# LifeBoardV1_2_stm.net
KiCad netlist of a schematic drawn in EAGLE
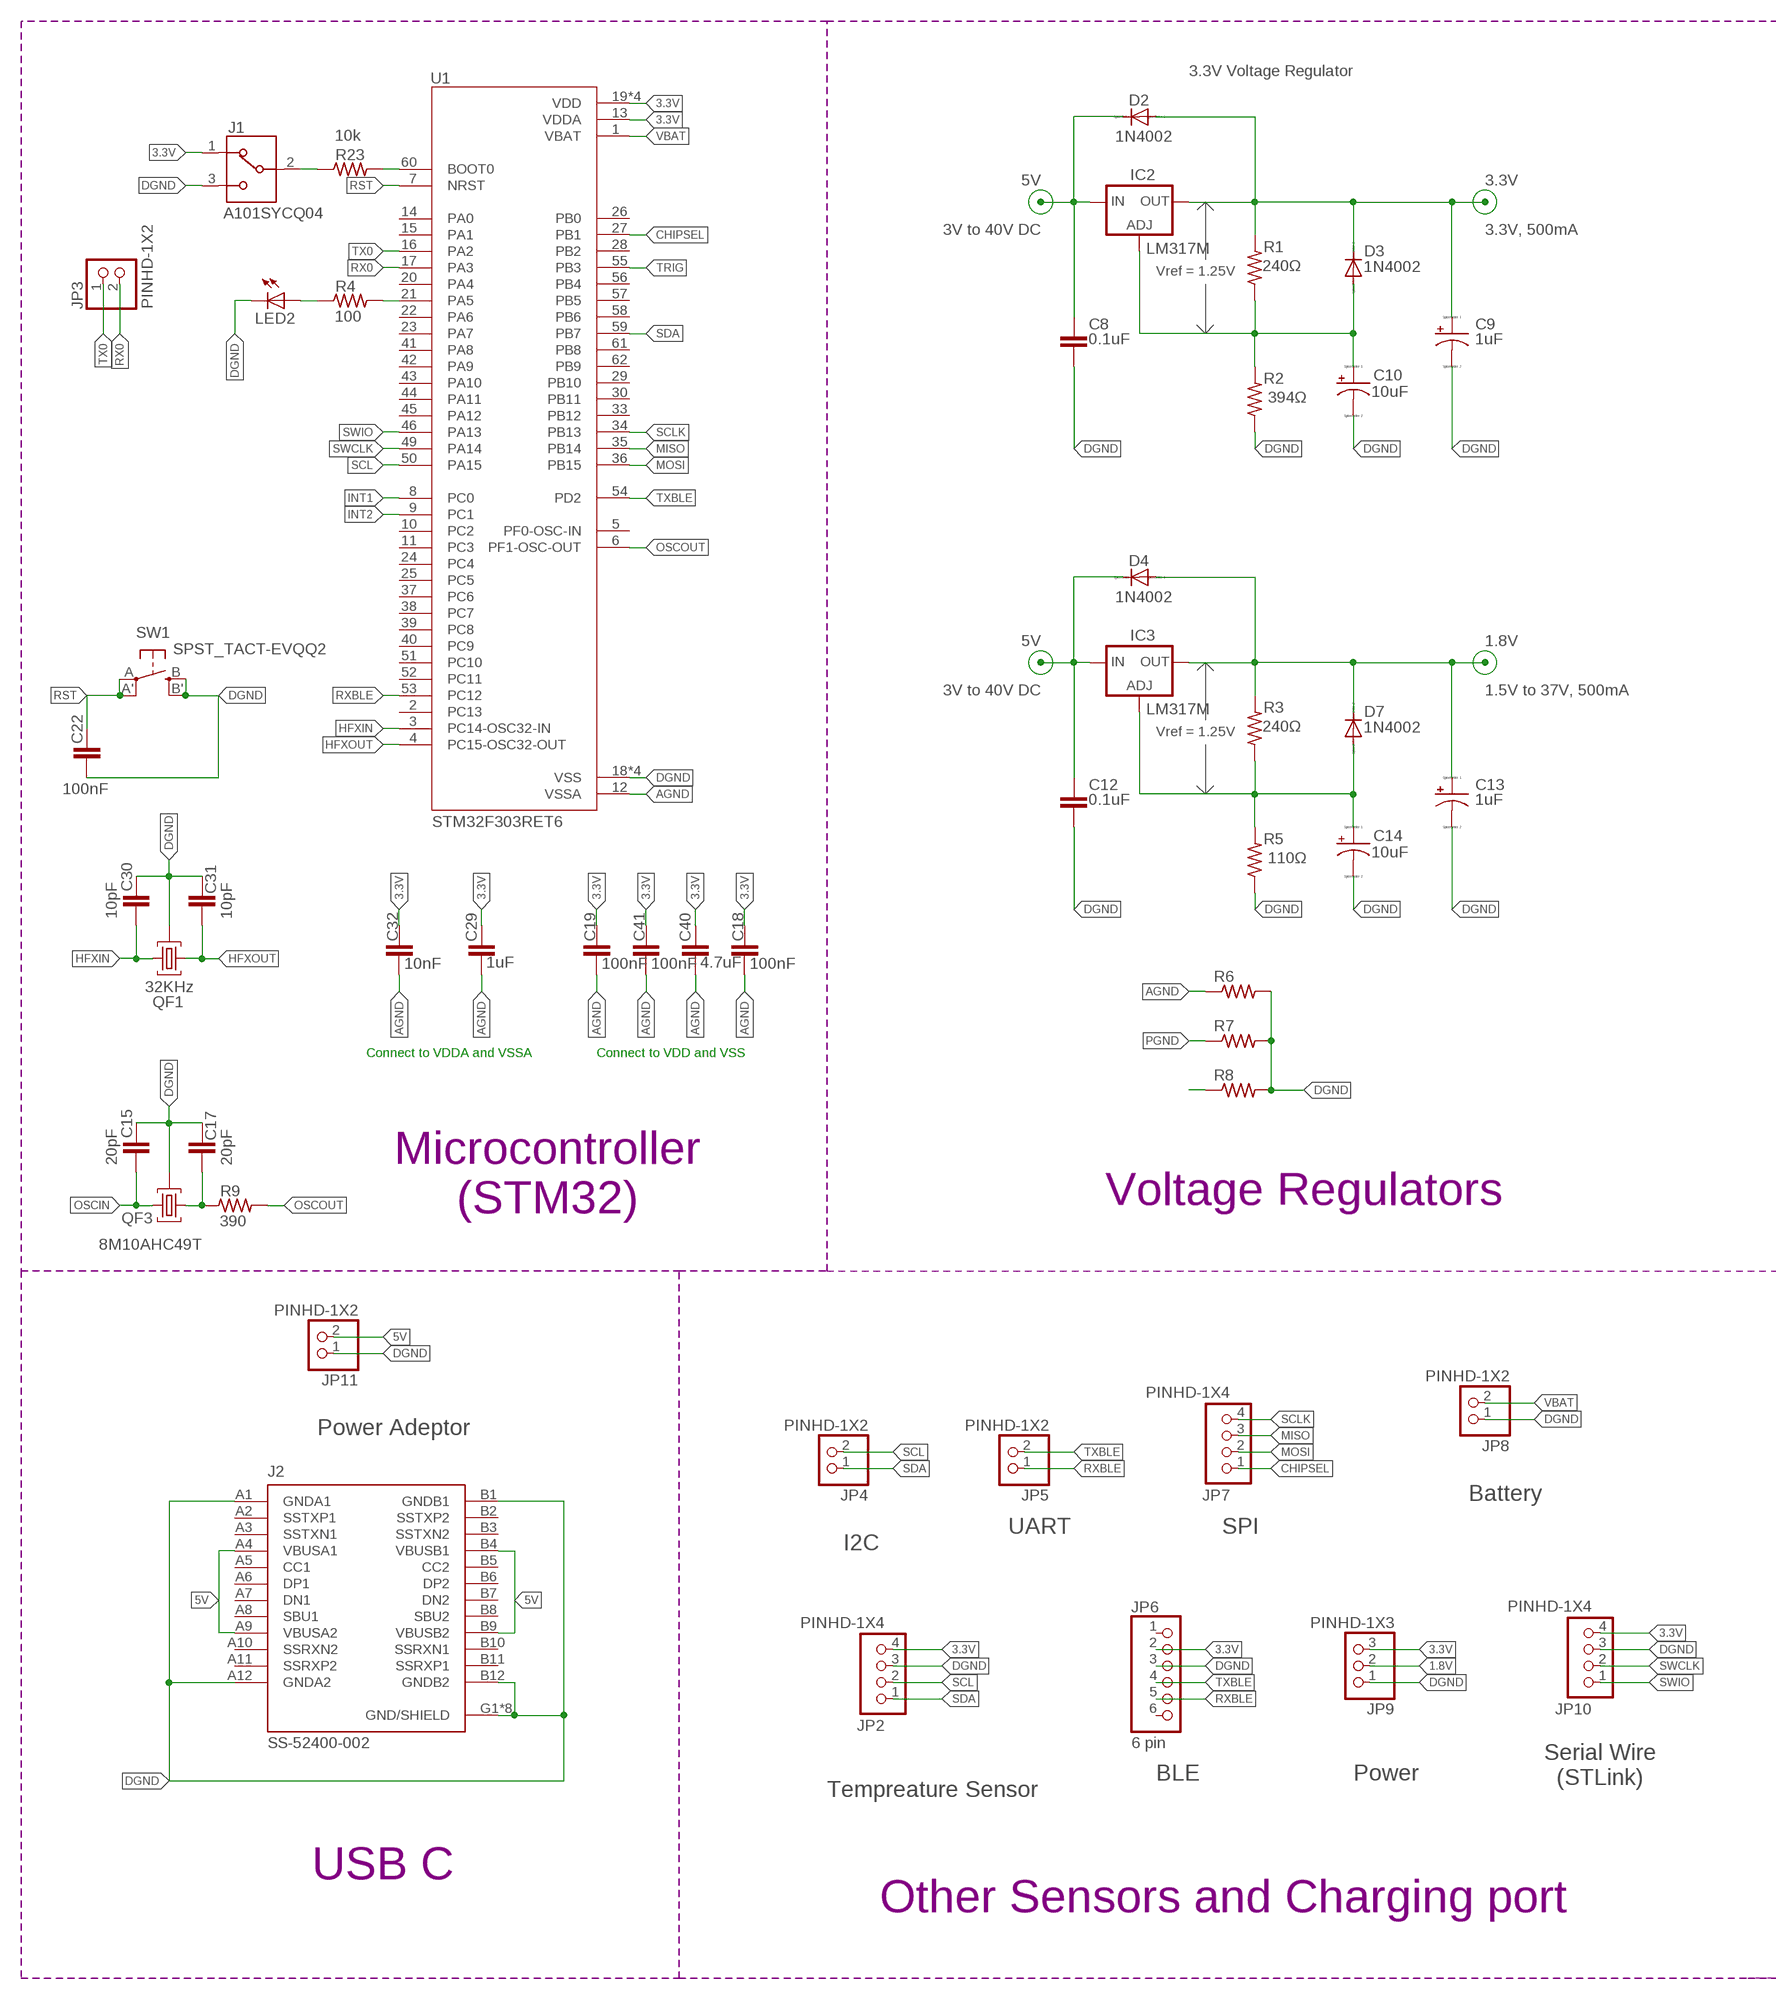
[diagram p0: schematic, sheet 1, part 1 of 2]
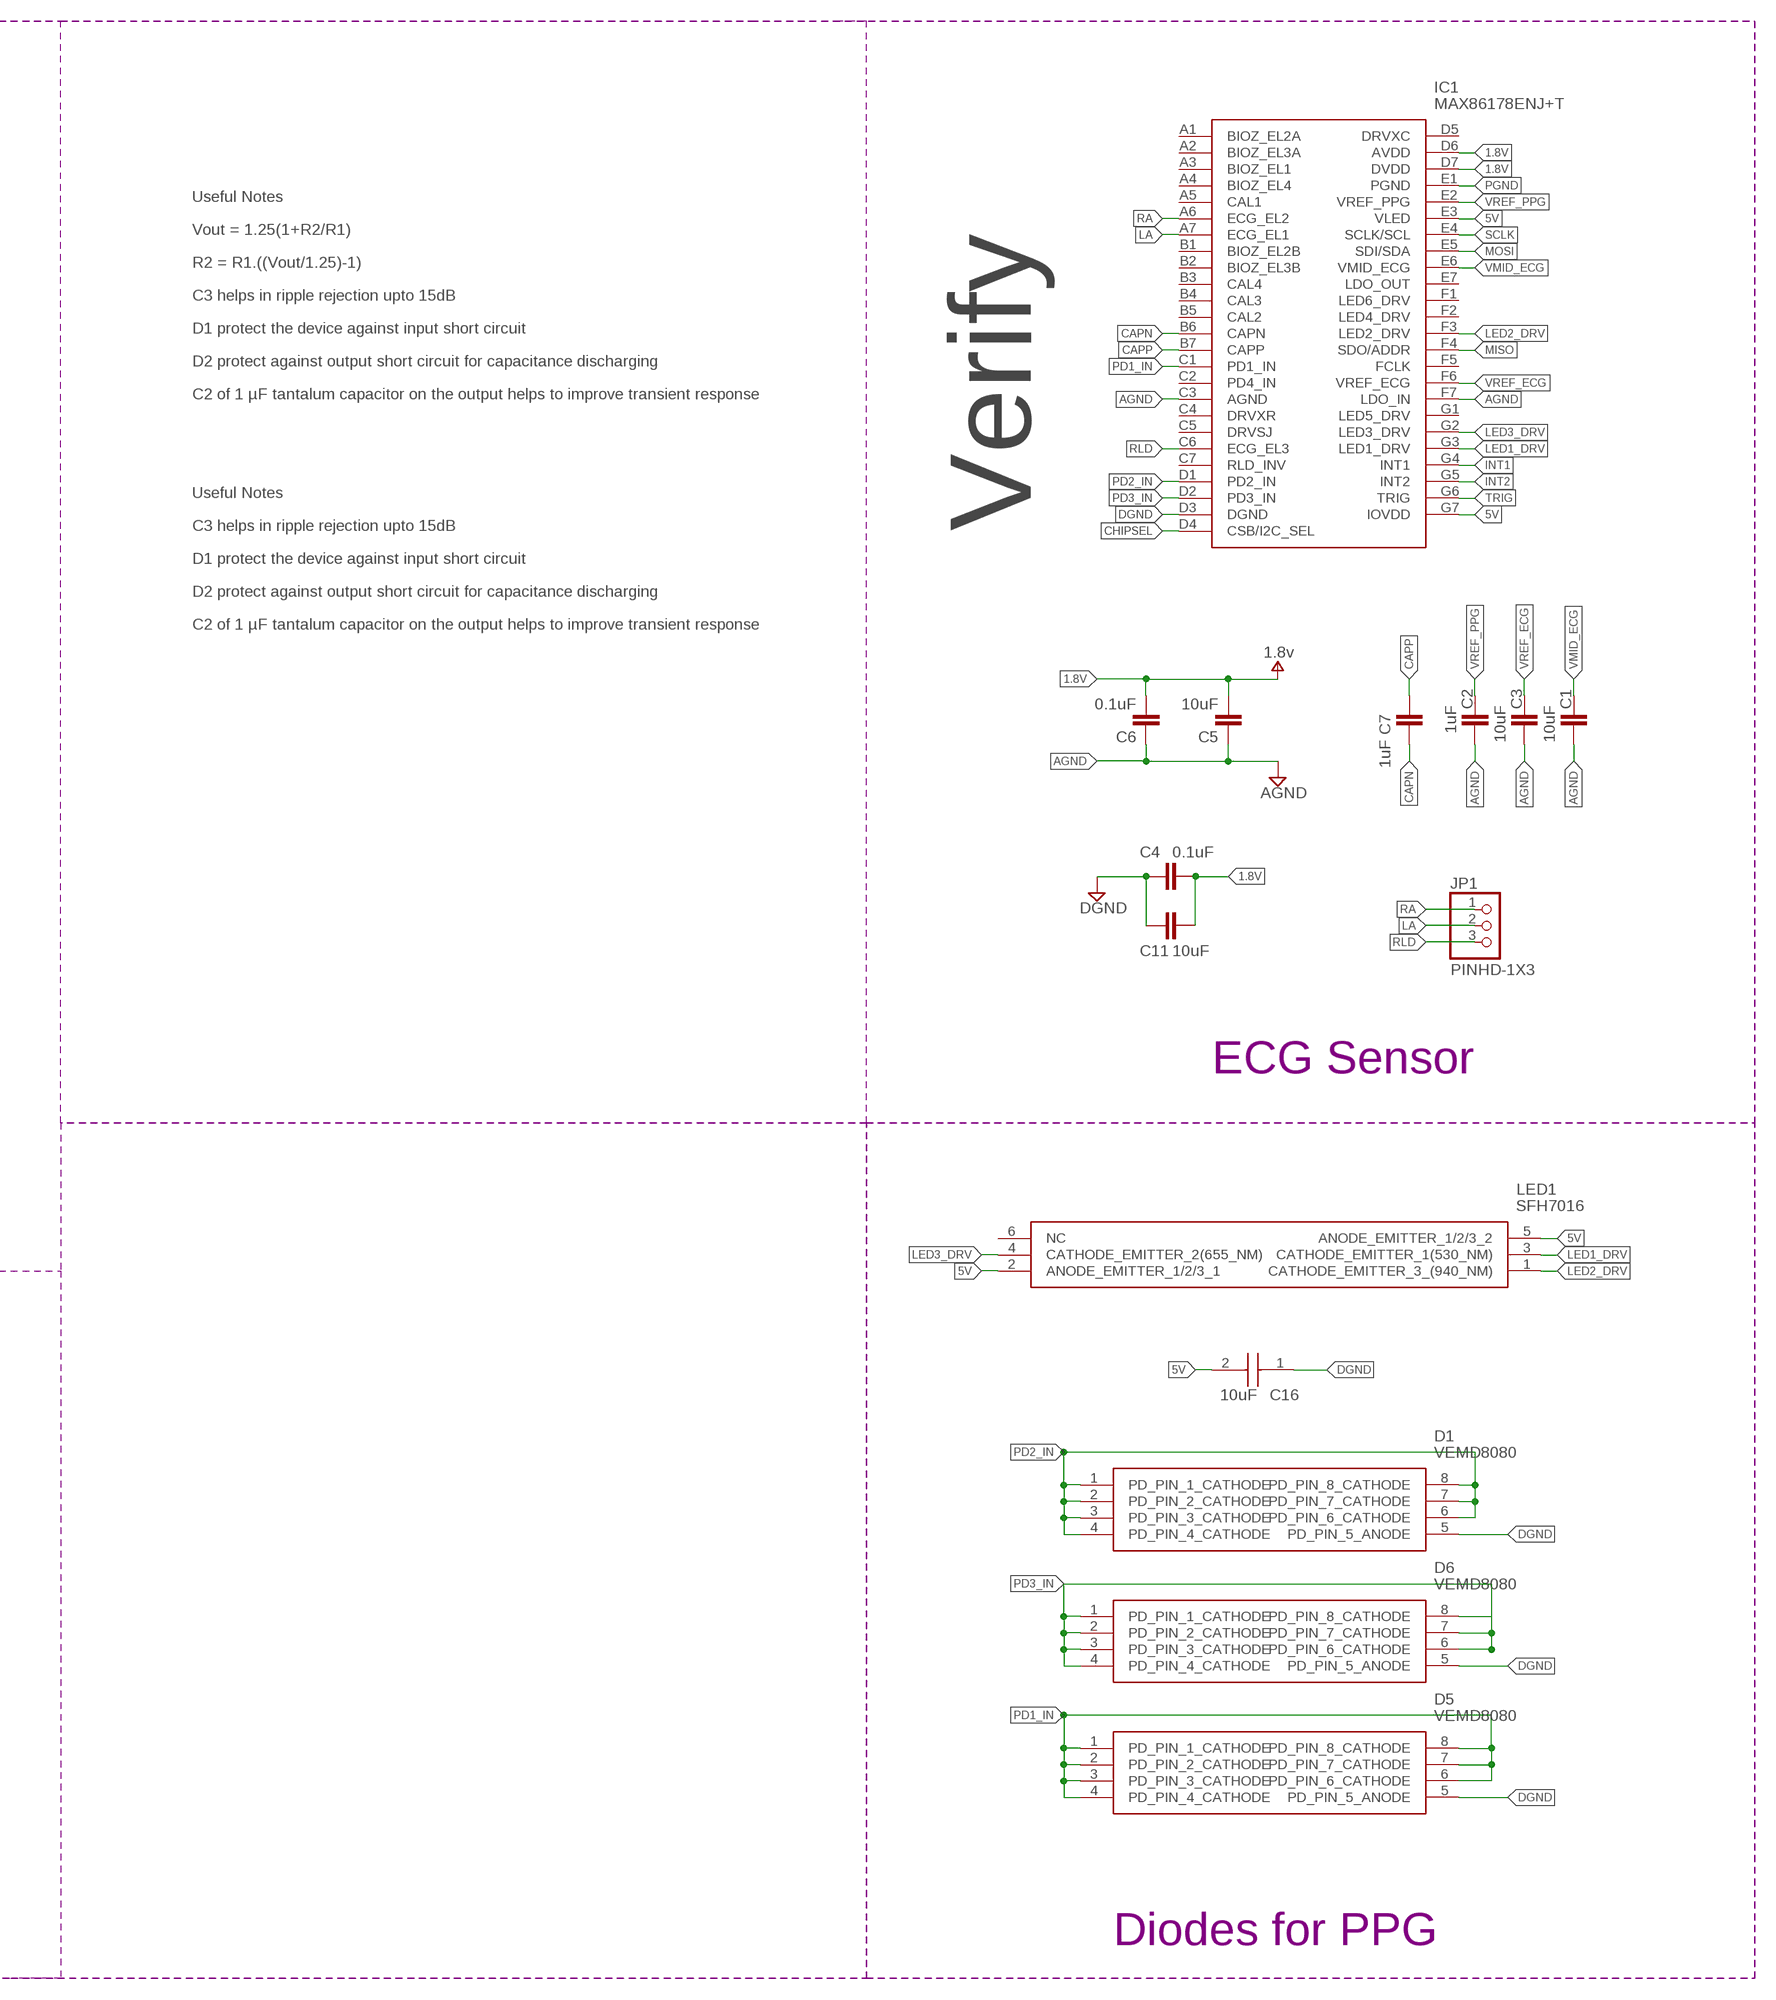
[diagram p1: schematic, sheet 1, part 2 of 2]

(export (version "E")
  (design (tool "Eeschema 10.0.6"))
  (components
    (comp (ref "C1")
      (value "10uF")
      (footprint "eagle-import:C0805")
      (libsource (lib "eagle-import") (part "C-EUC0805"))
    )
    (comp (ref "C2")
      (value "1uF")
      (footprint "eagle-import:C0805")
      (libsource (lib "eagle-import") (part "C-EUC0805"))
    )
    (comp (ref "C3")
      (value "10uF")
      (footprint "eagle-import:C0805")
      (libsource (lib "eagle-import") (part "C-EUC0805"))
    )
    (comp (ref "C4")
      (value "0.1uF")
      (footprint "eagle-import:C0805")
      (libsource (lib "eagle-import") (part "C-EUC0805"))
    )
    (comp (ref "C5")
      (value "10uF")
      (footprint "eagle-import:C0805")
      (libsource (lib "eagle-import") (part "C-EUC0805"))
    )
    (comp (ref "C6")
      (value "0.1uF")
      (footprint "eagle-import:C0805")
      (libsource (lib "eagle-import") (part "C-EUC0805"))
    )
    (comp (ref "C7")
      (value "1uF")
      (footprint "eagle-import:C0805")
      (libsource (lib "eagle-import") (part "C-EUC0805"))
    )
    (comp (ref "C8")
      (value "0.1uF")
      (footprint "eagle-import:C075-052X106")
      (libsource (lib "eagle-import") (part "C-EU075-052X106"))
    )
    (comp (ref "C9")
      (value "1uF")
      (footprint "eagle-import:085CS_1AR")
      (libsource (lib "eagle-import") (part "CPOL-US085CS-1AR"))
    )
    (comp (ref "C10")
      (value "10uF")
      (footprint "eagle-import:085CS_1AR")
      (libsource (lib "eagle-import") (part "CPOL-US085CS-1AR"))
    )
    (comp (ref "C11")
      (value "10uF")
      (footprint "eagle-import:C0805")
      (libsource (lib "eagle-import") (part "C-EUC0805"))
    )
    (comp (ref "C12")
      (value "0.1uF")
      (footprint "eagle-import:C075-052X106")
      (libsource (lib "eagle-import") (part "C-EU075-052X106"))
    )
    (comp (ref "C13")
      (value "1uF")
      (footprint "eagle-import:085CS_1AR")
      (libsource (lib "eagle-import") (part "CPOL-US085CS-1AR"))
    )
    (comp (ref "C14")
      (value "10uF")
      (footprint "eagle-import:085CS_1AR")
      (libsource (lib "eagle-import") (part "CPOL-US085CS-1AR"))
    )
    (comp (ref "C15")
      (value "20pF")
      (footprint "eagle-import:C0805")
      (libsource (lib "eagle-import") (part "C-EUC0805"))
    )
    (comp (ref "C16")
      (value "10uF")
      (footprint "eagle-import:CAPC1608X90N")
      (fields
        (field (name "ARROW_PART_NUMBER") "GRM188R61E106MA73L")
        (field (name "MOUSER_PART_NUMBER") "81-GRM188R61E106MA3L")
      )
      (libsource (lib "eagle-import") (part "GRM188R61E106MA73L"))
    )
    (comp (ref "C17")
      (value "20pF")
      (footprint "eagle-import:C0805")
      (libsource (lib "eagle-import") (part "C-EUC0805"))
    )
    (comp (ref "C18")
      (value "100nF")
      (footprint "eagle-import:C0805")
      (libsource (lib "eagle-import") (part "C-EUC0805"))
    )
    (comp (ref "C19")
      (value "100nF")
      (footprint "eagle-import:C0805")
      (libsource (lib "eagle-import") (part "C-EUC0805"))
    )
    (comp (ref "C22")
      (value "100nF")
      (footprint "eagle-import:C0805")
      (libsource (lib "eagle-import") (part "C-EUC0805"))
    )
    (comp (ref "C29")
      (value "1uF")
      (footprint "eagle-import:C0805")
      (libsource (lib "eagle-import") (part "C-EUC0805"))
    )
    (comp (ref "C30")
      (value "10pF")
      (footprint "eagle-import:C0805")
      (libsource (lib "eagle-import") (part "C-EUC0805"))
    )
    (comp (ref "C31")
      (value "10pF")
      (footprint "eagle-import:C0805")
      (libsource (lib "eagle-import") (part "C-EUC0805"))
    )
    (comp (ref "C32")
      (value "10nF")
      (footprint "eagle-import:C0805")
      (libsource (lib "eagle-import") (part "C-EUC0805"))
    )
    (comp (ref "C40")
      (value "4.7uF")
      (footprint "eagle-import:C0805")
      (libsource (lib "eagle-import") (part "C-EUC0805"))
    )
    (comp (ref "C41")
      (value "100nF")
      (footprint "eagle-import:C0805")
      (libsource (lib "eagle-import") (part "C-EUC0805"))
    )
    (comp (ref "D1")
      (value "VEMD8080")
      (footprint "eagle-import:VEMD8080")
      (fields (field (name "MOUSER_PART_NUMBER") "78-VEMD8080"))
      (libsource (lib "eagle-import") (part "VEMD8080"))
    )
    (comp (ref "D2")
      (value "1N4002")
      (footprint "eagle-import:DO41-10")
      (libsource (lib "eagle-import") (part "1N4004"))
    )
    (comp (ref "D3")
      (value "1N4002")
      (footprint "eagle-import:DO41-10")
      (libsource (lib "eagle-import") (part "1N4004"))
    )
    (comp (ref "D4")
      (value "1N4002")
      (footprint "eagle-import:DO41-10")
      (libsource (lib "eagle-import") (part "1N4004"))
    )
    (comp (ref "D5")
      (value "VEMD8080")
      (footprint "eagle-import:VEMD8080")
      (fields (field (name "MOUSER_PART_NUMBER") "78-VEMD8080"))
      (libsource (lib "eagle-import") (part "VEMD8080"))
    )
    (comp (ref "D6")
      (value "VEMD8080")
      (footprint "eagle-import:VEMD8080")
      (fields (field (name "MOUSER_PART_NUMBER") "78-VEMD8080"))
      (libsource (lib "eagle-import") (part "VEMD8080"))
    )
    (comp (ref "D7")
      (value "1N4002")
      (footprint "eagle-import:DO41-10")
      (libsource (lib "eagle-import") (part "1N4004"))
    )
    (comp (ref "IC1")
      (value "MAX86178ENJ+T")
      (footprint "eagle-import:BGA49C35P7X7_277X257X50")
      (fields (field (name "MOUSER_PART_NUMBER") "700-MAX86178ENJ+T"))
      (libsource (lib "eagle-import") (part "MAX86178ENJ+T"))
    )
    (comp (ref "IC2")
      (value "LM317MBSTT3")
      (footprint "eagle-import:SOT223")
      (fields (field (name "PARTNUMBER") "LM317M"))
      (libsource (lib "eagle-import") (part "LM317?MBSTT3"))
    )
    (comp (ref "IC3")
      (value "LM317MBSTT3")
      (footprint "eagle-import:SOT223")
      (fields (field (name "PARTNUMBER") "LM317M"))
      (libsource (lib "eagle-import") (part "LM317?MBSTT3"))
    )
    (comp (ref "J1")
      (value "A101SYCQ04")
      (footprint "eagle-import:TE_A101SYCQ04")
      (fields (field (name "COMMENT") "4-1825136-5") (field (name "MF") "TE Connectivity"))
      (libsource (lib "eagle-import") (part "A101SYCQ04"))
    )
    (comp (ref "J2")
      (value "SS-52400-002")
      (footprint "eagle-import:BELFUSE_SS-52400-002")
      (fields (field (name "MF") "Stewart Connector"))
      (libsource (lib "eagle-import") (part "SS-52400-002"))
    )
    (comp (ref "JP1")
      (value "PINHD-1X3")
      (footprint "eagle-import:1X03")
      (libsource (lib "eagle-import") (part "PINHD-1X3"))
    )
    (comp (ref "JP2")
      (value "PINHD-1X4")
      (footprint "eagle-import:1X04")
      (libsource (lib "eagle-import") (part "PINHD-1X4"))
    )
    (comp (ref "JP3")
      (value "PINHD-1X2")
      (footprint "eagle-import:1X02")
      (libsource (lib "eagle-import") (part "PINHD-1X2"))
    )
    (comp (ref "JP4")
      (value "PINHD-1X2")
      (footprint "eagle-import:1X02")
      (libsource (lib "eagle-import") (part "PINHD-1X2"))
    )
    (comp (ref "JP5")
      (value "PINHD-1X2")
      (footprint "eagle-import:1X02")
      (libsource (lib "eagle-import") (part "PINHD-1X2"))
    )
    (comp (ref "JP6")
      (value "6 pin")
      (footprint "eagle-import:1X06")
      (libsource (lib "eagle-import") (part "PINHD-1X6"))
    )
    (comp (ref "JP7")
      (value "PINHD-1X4")
      (footprint "eagle-import:1X04")
      (libsource (lib "eagle-import") (part "PINHD-1X4"))
    )
    (comp (ref "JP8")
      (value "PINHD-1X2")
      (footprint "eagle-import:1X02")
      (libsource (lib "eagle-import") (part "PINHD-1X2"))
    )
    (comp (ref "JP9")
      (value "PINHD-1X3")
      (footprint "eagle-import:1X03")
      (libsource (lib "eagle-import") (part "PINHD-1X3"))
    )
    (comp (ref "JP10")
      (value "PINHD-1X4")
      (footprint "eagle-import:1X04")
      (libsource (lib "eagle-import") (part "PINHD-1X4"))
    )
    (comp (ref "JP11")
      (value "PINHD-1X2")
      (footprint "eagle-import:1X02")
      (libsource (lib "eagle-import") (part "PINHD-1X2"))
    )
    (comp (ref "LED1")
      (value "SFH7016")
      (footprint "eagle-import:SFH7016")
      (libsource (lib "eagle-import") (part "SFH7016"))
    )
    (comp (ref "LED2")
      (value "LEDCHIP-LED0805")
      (footprint "eagle-import:CHIP-LED0805")
      (libsource (lib "eagle-import") (part "LEDCHIP-LED0805"))
    )
    (comp (ref "QF1")
      (value "32KHz")
      (footprint "eagle-import:HC49U")
      (libsource (lib "eagle-import") (part "8M10AHC49T"))
    )
    (comp (ref "QF3")
      (value "8M10AHC49T")
      (footprint "eagle-import:HC49U")
      (libsource (lib "eagle-import") (part "8M10AHC49T"))
    )
    (comp (ref "R1")
      (value "240Ω")
      (footprint "eagle-import:M0805")
      (libsource (lib "eagle-import") (part "resistor_348_R-US_M0805"))
    )
    (comp (ref "R2")
      (value "394Ω")
      (footprint "eagle-import:M0805")
      (libsource (lib "eagle-import") (part "resistor_348_R-US_M0805"))
    )
    (comp (ref "R3")
      (value "240Ω")
      (footprint "eagle-import:M0805")
      (libsource (lib "eagle-import") (part "resistor_348_R-US_M0805"))
    )
    (comp (ref "R4")
      (value "100")
      (footprint "eagle-import:M1206")
      (libsource (lib "eagle-import") (part "R-US_M1206"))
    )
    (comp (ref "R5")
      (value "110Ω")
      (footprint "eagle-import:M0805")
      (libsource (lib "eagle-import") (part "resistor_348_R-US_M0805"))
    )
    (comp (ref "R6")
      (value "R-US_M0805")
      (footprint "eagle-import:M0805")
      (libsource (lib "eagle-import") (part "R-US_M0805"))
    )
    (comp (ref "R7")
      (value "R-US_M0805")
      (footprint "eagle-import:M0805")
      (libsource (lib "eagle-import") (part "R-US_M0805"))
    )
    (comp (ref "R8")
      (value "R-US_M0805")
      (footprint "eagle-import:M0805")
      (libsource (lib "eagle-import") (part "R-US_M0805"))
    )
    (comp (ref "R9")
      (value "390")
      (footprint "eagle-import:M1206")
      (libsource (lib "eagle-import") (part "R-US_M1206"))
    )
    (comp (ref "R23")
      (value "10k")
      (footprint "eagle-import:M1206")
      (libsource (lib "eagle-import") (part "R-US_M1206"))
    )
    (comp (ref "SW1")
      (value "SPST_TACT-EVQQ2")
      (footprint "eagle-import:EVQ-Q2")
      (libsource (lib "eagle-import") (part "SPST_TACT-EVQQ2"))
    )
    (comp (ref "U1")
      (value "STM32F303RET6")
      (footprint "eagle-import:QFP50P1200X1200X160-64N")
      (fields (field (name "MF") "STMicroelectronics"))
      (libsource (lib "eagle-import") (part "STM32F303RET6"))
    )
  )
  (nets
    (net (code "1") (name "1.8V") (class "Default")
      (node (ref "C11") (pin "2") (pinfunction "2_2") (pintype "passive"))
      (node (ref "C13") (pin "+") (pinfunction "+_+") (pintype "passive"))
      (node (ref "C4") (pin "2") (pinfunction "2_2") (pintype "passive"))
      (node (ref "C5") (pin "2") (pinfunction "2_2") (pintype "passive"))
      (node (ref "C6") (pin "2") (pinfunction "2_2") (pintype "passive"))
      (node (ref "D4") (pin "A") (pinfunction "A_A") (pintype "passive"))
      (node (ref "D7") (pin "C") (pinfunction "C_C") (pintype "passive"))
      (node (ref "IC1") (pin "D6") (pinfunction "AVDD_D6") (pintype "bidirectional"))
      (node (ref "IC1") (pin "D7") (pinfunction "DVDD_D7") (pintype "bidirectional"))
      (node (ref "IC3") (pin "4") (pinfunction "OUT_4") (pintype "passive"))
      (node (ref "JP9") (pin "2") (pinfunction "2_2") (pintype "passive"))
      (node (ref "R3") (pin "2") (pinfunction "2_2") (pintype "passive"))
    )
    (net (code "2") (name "3.3V") (class "Default")
      (node (ref "C18") (pin "1") (pinfunction "1_1") (pintype "passive"))
      (node (ref "C19") (pin "1") (pinfunction "1_1") (pintype "passive"))
      (node (ref "C29") (pin "1") (pinfunction "1_1") (pintype "passive"))
      (node (ref "C32") (pin "1") (pinfunction "1_1") (pintype "passive"))
      (node (ref "C40") (pin "1") (pinfunction "1_1") (pintype "passive"))
      (node (ref "C41") (pin "1") (pinfunction "1_1") (pintype "passive"))
      (node (ref "C9") (pin "+") (pinfunction "+_+") (pintype "passive"))
      (node (ref "D2") (pin "A") (pinfunction "A_A") (pintype "passive"))
      (node (ref "D3") (pin "C") (pinfunction "C_C") (pintype "passive"))
      (node (ref "IC2") (pin "4") (pinfunction "OUT_4") (pintype "passive"))
      (node (ref "J1") (pin "1") (pinfunction "1_1") (pintype "passive"))
      (node (ref "JP10") (pin "4") (pinfunction "4_4") (pintype "passive"))
      (node (ref "JP2") (pin "4") (pinfunction "4_4") (pintype "passive"))
      (node (ref "JP6") (pin "2") (pinfunction "2_2") (pintype "passive"))
      (node (ref "JP9") (pin "3") (pinfunction "3_3") (pintype "passive"))
      (node (ref "R1") (pin "2") (pinfunction "2_2") (pintype "passive"))
      (node (ref "U1") (pin "13") (pinfunction "VDDA_13") (pintype "power_in"))
      (node (ref "U1") (pin "19") (pinfunction "VDD_19") (pintype "power_in"))
      (node (ref "U1") (pin "32") (pinfunction "VDD_32") (pintype "power_in"))
      (node (ref "U1") (pin "48") (pinfunction "VDD_48") (pintype "power_in"))
      (node (ref "U1") (pin "64") (pinfunction "VDD_64") (pintype "power_in"))
    )
    (net (code "3") (name "5V") (class "Default")
      (node (ref "C12") (pin "1") (pinfunction "1_1") (pintype "passive"))
      (node (ref "C16") (pin "2") (pinfunction "2_2") (pintype "bidirectional"))
      (node (ref "C8") (pin "1") (pinfunction "1_1") (pintype "passive"))
      (node (ref "D2") (pin "C") (pinfunction "C_C") (pintype "passive"))
      (node (ref "D4") (pin "C") (pinfunction "C_C") (pintype "passive"))
      (node (ref "IC1") (pin "E3") (pinfunction "VLED_E3") (pintype "bidirectional"))
      (node (ref "IC1") (pin "G7") (pinfunction "IOVDD_G7") (pintype "bidirectional"))
      (node (ref "IC2") (pin "3") (pinfunction "IN_3") (pintype "input"))
      (node (ref "IC3") (pin "3") (pinfunction "IN_3") (pintype "input"))
      (node (ref "J2") (pin "A4") (pinfunction "VBUSA1_A4") (pintype "power_in"))
      (node (ref "J2") (pin "A9") (pinfunction "VBUSA2_A9") (pintype "power_in"))
      (node (ref "J2") (pin "B4") (pinfunction "VBUSB1_B4") (pintype "power_in"))
      (node (ref "J2") (pin "B9") (pinfunction "VBUSB2_B9") (pintype "power_in"))
      (node (ref "JP11") (pin "2") (pinfunction "2_2") (pintype "passive"))
      (node (ref "LED1") (pin "2") (pinfunction "ANODE_EMITTER_1/2/3_1_2") (pintype "bidirectional"))
      (node (ref "LED1") (pin "5") (pinfunction "ANODE_EMITTER_1/2/3_2_5") (pintype "bidirectional"))
    )
    (net (code "4") (name "AGND") (class "Default")
      (node (ref "C1") (pin "1") (pinfunction "1_1") (pintype "passive"))
      (node (ref "C18") (pin "2") (pinfunction "2_2") (pintype "passive"))
      (node (ref "C19") (pin "2") (pinfunction "2_2") (pintype "passive"))
      (node (ref "C2") (pin "1") (pinfunction "1_1") (pintype "passive"))
      (node (ref "C29") (pin "2") (pinfunction "2_2") (pintype "passive"))
      (node (ref "C3") (pin "1") (pinfunction "1_1") (pintype "passive"))
      (node (ref "C32") (pin "2") (pinfunction "2_2") (pintype "passive"))
      (node (ref "C40") (pin "2") (pinfunction "2_2") (pintype "passive"))
      (node (ref "C41") (pin "2") (pinfunction "2_2") (pintype "passive"))
      (node (ref "C5") (pin "1") (pinfunction "1_1") (pintype "passive"))
      (node (ref "C6") (pin "1") (pinfunction "1_1") (pintype "passive"))
      (node (ref "IC1") (pin "C3") (pinfunction "AGND_C3") (pintype "bidirectional"))
      (node (ref "IC1") (pin "F7") (pinfunction "LDO_IN_F7") (pintype "bidirectional"))
      (node (ref "R6") (pin "1") (pinfunction "1_1") (pintype "passive"))
      (node (ref "U1") (pin "12") (pinfunction "VSSA_12") (pintype "power_in"))
    )
    (net (code "5") (name "CAPN") (class "Default")
      (node (ref "C7") (pin "2") (pinfunction "2_2") (pintype "passive"))
      (node (ref "IC1") (pin "B6") (pinfunction "CAPN_B6") (pintype "bidirectional"))
    )
    (net (code "6") (name "CAPP") (class "Default")
      (node (ref "C7") (pin "1") (pinfunction "1_1") (pintype "passive"))
      (node (ref "IC1") (pin "B7") (pinfunction "CAPP_B7") (pintype "bidirectional"))
    )
    (net (code "7") (name "CHIPSEL") (class "Default")
      (node (ref "IC1") (pin "D4") (pinfunction "CSB/I2C_SEL_D4") (pintype "bidirectional"))
      (node (ref "JP7") (pin "1") (pinfunction "1_1") (pintype "passive"))
      (node (ref "U1") (pin "27") (pinfunction "PB1_27") (pintype "bidirectional"))
    )
    (net (code "8") (name "DGND") (class "Default")
      (node (ref "C10") (pin "-") (pinfunction "-_-") (pintype "passive"))
      (node (ref "C11") (pin "1") (pinfunction "1_1") (pintype "passive"))
      (node (ref "C12") (pin "2") (pinfunction "2_2") (pintype "passive"))
      (node (ref "C13") (pin "-") (pinfunction "-_-") (pintype "passive"))
      (node (ref "C14") (pin "-") (pinfunction "-_-") (pintype "passive"))
      (node (ref "C15") (pin "1") (pinfunction "1_1") (pintype "passive"))
      (node (ref "C16") (pin "1") (pinfunction "1_1") (pintype "bidirectional"))
      (node (ref "C17") (pin "1") (pinfunction "1_1") (pintype "passive"))
      (node (ref "C22") (pin "2") (pinfunction "2_2") (pintype "passive"))
      (node (ref "C30") (pin "1") (pinfunction "1_1") (pintype "passive"))
      (node (ref "C31") (pin "1") (pinfunction "1_1") (pintype "passive"))
      (node (ref "C4") (pin "1") (pinfunction "1_1") (pintype "passive"))
      (node (ref "C8") (pin "2") (pinfunction "2_2") (pintype "passive"))
      (node (ref "C9") (pin "-") (pinfunction "-_-") (pintype "passive"))
      (node (ref "D1") (pin "5") (pinfunction "PD_PIN_5_ANODE_5") (pintype "bidirectional"))
      (node (ref "D5") (pin "5") (pinfunction "PD_PIN_5_ANODE_5") (pintype "bidirectional"))
      (node (ref "D6") (pin "5") (pinfunction "PD_PIN_5_ANODE_5") (pintype "bidirectional"))
      (node (ref "IC1") (pin "D3") (pinfunction "DGND_D3") (pintype "bidirectional"))
      (node (ref "J1") (pin "3") (pinfunction "3_3") (pintype "passive"))
      (node (ref "J2") (pin "A1") (pinfunction "GNDA1_A1") (pintype "power_in"))
      (node (ref "J2") (pin "A12") (pinfunction "GNDA2_A12") (pintype "power_in"))
      (node (ref "J2") (pin "B1") (pinfunction "GNDB1_B1") (pintype "power_in"))
      (node (ref "J2") (pin "B12") (pinfunction "GNDB2_B12") (pintype "power_in"))
      (node (ref "J2") (pin "G1") (pinfunction "GND/SHIELD_G1") (pintype "power_in"))
      (node (ref "J2") (pin "G2") (pinfunction "GND/SHIELD_G2") (pintype "power_in"))
      (node (ref "J2") (pin "G3") (pinfunction "GND/SHIELD_G3") (pintype "power_in"))
      (node (ref "J2") (pin "G4") (pinfunction "GND/SHIELD_G4") (pintype "power_in"))
      (node (ref "J2") (pin "S1") (pinfunction "GND/SHIELD_S1") (pintype "power_in"))
      (node (ref "J2") (pin "S2") (pinfunction "GND/SHIELD_S2") (pintype "power_in"))
      (node (ref "J2") (pin "S3") (pinfunction "GND/SHIELD_S3") (pintype "power_in"))
      (node (ref "J2") (pin "S4") (pinfunction "GND/SHIELD_S4") (pintype "power_in"))
      (node (ref "JP10") (pin "3") (pinfunction "3_3") (pintype "passive"))
      (node (ref "JP11") (pin "1") (pinfunction "1_1") (pintype "passive"))
      (node (ref "JP2") (pin "3") (pinfunction "3_3") (pintype "passive"))
      (node (ref "JP6") (pin "3") (pinfunction "3_3") (pintype "passive"))
      (node (ref "JP8") (pin "1") (pinfunction "1_1") (pintype "passive"))
      (node (ref "JP9") (pin "1") (pinfunction "1_1") (pintype "passive"))
      (node (ref "LED2") (pin "C") (pinfunction "C_C") (pintype "passive"))
      (node (ref "QF1") (pin "2") (pinfunction "2_2") (pintype "passive"))
      (node (ref "QF3") (pin "2") (pinfunction "2_2") (pintype "passive"))
      (node (ref "R2") (pin "1") (pinfunction "1_1") (pintype "passive"))
      (node (ref "R5") (pin "1") (pinfunction "1_1") (pintype "passive"))
      (node (ref "R6") (pin "2") (pinfunction "2_2") (pintype "passive"))
      (node (ref "R7") (pin "2") (pinfunction "2_2") (pintype "passive"))
      (node (ref "R8") (pin "2") (pinfunction "2_2") (pintype "passive"))
      (node (ref "SW1") (pin "B") (pinfunction "S_B") (pintype "passive"))
      (node (ref "SW1") (pin "B'") (pinfunction "S1_B'") (pintype "passive"))
      (node (ref "U1") (pin "18") (pinfunction "VSS_18") (pintype "power_in"))
      (node (ref "U1") (pin "31") (pinfunction "VSS_31") (pintype "power_in"))
      (node (ref "U1") (pin "47") (pinfunction "VSS_47") (pintype "power_in"))
      (node (ref "U1") (pin "63") (pinfunction "VSS_63") (pintype "power_in"))
    )
    (net (code "9") (name "HFXIN") (class "Default")
      (node (ref "C30") (pin "2") (pinfunction "2_2") (pintype "passive"))
      (node (ref "QF1") (pin "3") (pinfunction "3_3") (pintype "passive"))
      (node (ref "U1") (pin "3") (pinfunction "PC14-OSC32-IN_3") (pintype "bidirectional"))
    )
    (net (code "10") (name "HFXOUT") (class "Default")
      (node (ref "C31") (pin "2") (pinfunction "2_2") (pintype "passive"))
      (node (ref "QF1") (pin "1") (pinfunction "1_1") (pintype "passive"))
      (node (ref "U1") (pin "4") (pinfunction "PC15-OSC32-OUT_4") (pintype "bidirectional"))
    )
    (net (code "11") (name "INT1") (class "Default")
      (node (ref "IC1") (pin "G4") (pinfunction "INT1_G4") (pintype "bidirectional"))
      (node (ref "U1") (pin "8") (pinfunction "PC0_8") (pintype "bidirectional"))
    )
    (net (code "12") (name "INT2") (class "Default")
      (node (ref "IC1") (pin "G5") (pinfunction "INT2_G5") (pintype "bidirectional"))
      (node (ref "U1") (pin "9") (pinfunction "PC1_9") (pintype "bidirectional"))
    )
    (net (code "13") (name "LA") (class "Default")
      (node (ref "IC1") (pin "A7") (pinfunction "ECG_EL1_A7") (pintype "bidirectional"))
      (node (ref "JP1") (pin "2") (pinfunction "2_2") (pintype "passive"))
    )
    (net (code "14") (name "LED1_DRV") (class "Default")
      (node (ref "IC1") (pin "G3") (pinfunction "LED1_DRV_G3") (pintype "bidirectional"))
      (node (ref "LED1") (pin "3") (pinfunction "CATHODE_EMITTER_1(530_NM)_3") (pintype "bidirectional"))
    )
    (net (code "15") (name "LED2_DRV") (class "Default")
      (node (ref "IC1") (pin "F3") (pinfunction "LED2_DRV_F3") (pintype "bidirectional"))
      (node (ref "LED1") (pin "1") (pinfunction "CATHODE_EMITTER_3_(940_NM)_1") (pintype "bidirectional"))
    )
    (net (code "16") (name "LED3_DRV") (class "Default")
      (node (ref "IC1") (pin "G2") (pinfunction "LED3_DRV_G2") (pintype "bidirectional"))
      (node (ref "LED1") (pin "4") (pinfunction "CATHODE_EMITTER_2(655_NM)_4") (pintype "bidirectional"))
    )
    (net (code "17") (name "MISO") (class "Default")
      (node (ref "IC1") (pin "F4") (pinfunction "SDO/ADDR_F4") (pintype "bidirectional"))
      (node (ref "JP7") (pin "3") (pinfunction "3_3") (pintype "passive"))
      (node (ref "U1") (pin "35") (pinfunction "PB14_35") (pintype "bidirectional"))
    )
    (net (code "18") (name "MOSI") (class "Default")
      (node (ref "IC1") (pin "E5") (pinfunction "SDI/SDA_E5") (pintype "bidirectional"))
      (node (ref "JP7") (pin "2") (pinfunction "2_2") (pintype "passive"))
      (node (ref "U1") (pin "36") (pinfunction "PB15_36") (pintype "bidirectional"))
    )
    (net (code "19") (name "Net-(C17-Pad2)") (class "Default")
      (node (ref "C17") (pin "2") (pinfunction "2_2") (pintype "passive"))
      (node (ref "QF3") (pin "1") (pinfunction "1_1") (pintype "passive"))
      (node (ref "R9") (pin "1") (pinfunction "1_1") (pintype "passive"))
    )
    (net (code "20") (name "Net-(IC2-ADJ)") (class "Default")
      (node (ref "C10") (pin "+") (pinfunction "+_+") (pintype "passive"))
      (node (ref "D3") (pin "A") (pinfunction "A_A") (pintype "passive"))
      (node (ref "IC2") (pin "1") (pinfunction "ADJ_1") (pintype "input"))
      (node (ref "R1") (pin "1") (pinfunction "1_1") (pintype "passive"))
      (node (ref "R2") (pin "2") (pinfunction "2_2") (pintype "passive"))
    )
    (net (code "21") (name "Net-(IC3-ADJ)") (class "Default")
      (node (ref "C14") (pin "+") (pinfunction "+_+") (pintype "passive"))
      (node (ref "D7") (pin "A") (pinfunction "A_A") (pintype "passive"))
      (node (ref "IC3") (pin "1") (pinfunction "ADJ_1") (pintype "input"))
      (node (ref "R3") (pin "1") (pinfunction "1_1") (pintype "passive"))
      (node (ref "R5") (pin "2") (pinfunction "2_2") (pintype "passive"))
    )
    (net (code "22") (name "Net-(J1-Pad2)") (class "Default")
      (node (ref "J1") (pin "2") (pinfunction "2_2") (pintype "passive"))
      (node (ref "R23") (pin "1") (pinfunction "1_1") (pintype "passive"))
    )
    (net (code "23") (name "Net-(LED2-PadA)") (class "Default")
      (node (ref "LED2") (pin "A") (pinfunction "A_A") (pintype "passive"))
      (node (ref "R4") (pin "1") (pinfunction "1_1") (pintype "passive"))
    )
    (net (code "24") (name "Net-(U1-BOOT0)") (class "Default")
      (node (ref "R23") (pin "2") (pinfunction "2_2") (pintype "passive"))
      (node (ref "U1") (pin "60") (pinfunction "BOOT0_60") (pintype "input"))
    )
    (net (code "25") (name "Net-(U1-PA5)") (class "Default")
      (node (ref "R4") (pin "2") (pinfunction "2_2") (pintype "passive"))
      (node (ref "U1") (pin "21") (pinfunction "PA5_21") (pintype "bidirectional"))
    )
    (net (code "26") (name "OSCIN") (class "Default")
      (node (ref "C15") (pin "2") (pinfunction "2_2") (pintype "passive"))
      (node (ref "QF3") (pin "3") (pinfunction "3_3") (pintype "passive"))
    )
    (net (code "27") (name "OSCOUT") (class "Default")
      (node (ref "R9") (pin "2") (pinfunction "2_2") (pintype "passive"))
      (node (ref "U1") (pin "6") (pinfunction "PF1-OSC-OUT_6") (pintype "bidirectional"))
    )
    (net (code "28") (name "PD1_IN") (class "Default")
      (node (ref "D5") (pin "1") (pinfunction "PD_PIN_1_CATHODE_1") (pintype "bidirectional"))
      (node (ref "D5") (pin "2") (pinfunction "PD_PIN_2_CATHODE_2") (pintype "bidirectional"))
      (node (ref "D5") (pin "3") (pinfunction "PD_PIN_3_CATHODE_3") (pintype "bidirectional"))
      (node (ref "D5") (pin "4") (pinfunction "PD_PIN_4_CATHODE_4") (pintype "bidirectional"))
      (node (ref "D5") (pin "6") (pinfunction "PD_PIN_6_CATHODE_6") (pintype "bidirectional"))
      (node (ref "D5") (pin "7") (pinfunction "PD_PIN_7_CATHODE_7") (pintype "bidirectional"))
      (node (ref "D5") (pin "8") (pinfunction "PD_PIN_8_CATHODE_8") (pintype "bidirectional"))
      (node (ref "IC1") (pin "C1") (pinfunction "PD1_IN_C1") (pintype "bidirectional"))
    )
    (net (code "29") (name "PD2_IN") (class "Default")
      (node (ref "D1") (pin "1") (pinfunction "PD_PIN_1_CATHODE_1") (pintype "bidirectional"))
      (node (ref "D1") (pin "2") (pinfunction "PD_PIN_2_CATHODE_2") (pintype "bidirectional"))
      (node (ref "D1") (pin "3") (pinfunction "PD_PIN_3_CATHODE_3") (pintype "bidirectional"))
      (node (ref "D1") (pin "4") (pinfunction "PD_PIN_4_CATHODE_4") (pintype "bidirectional"))
      (node (ref "D1") (pin "6") (pinfunction "PD_PIN_6_CATHODE_6") (pintype "bidirectional"))
      (node (ref "D1") (pin "7") (pinfunction "PD_PIN_7_CATHODE_7") (pintype "bidirectional"))
      (node (ref "D1") (pin "8") (pinfunction "PD_PIN_8_CATHODE_8") (pintype "bidirectional"))
      (node (ref "IC1") (pin "D1") (pinfunction "PD2_IN_D1") (pintype "bidirectional"))
    )
    (net (code "30") (name "PD3_IN") (class "Default")
      (node (ref "D6") (pin "1") (pinfunction "PD_PIN_1_CATHODE_1") (pintype "bidirectional"))
      (node (ref "D6") (pin "2") (pinfunction "PD_PIN_2_CATHODE_2") (pintype "bidirectional"))
      (node (ref "D6") (pin "3") (pinfunction "PD_PIN_3_CATHODE_3") (pintype "bidirectional"))
      (node (ref "D6") (pin "4") (pinfunction "PD_PIN_4_CATHODE_4") (pintype "bidirectional"))
      (node (ref "D6") (pin "6") (pinfunction "PD_PIN_6_CATHODE_6") (pintype "bidirectional"))
      (node (ref "D6") (pin "7") (pinfunction "PD_PIN_7_CATHODE_7") (pintype "bidirectional"))
      (node (ref "D6") (pin "8") (pinfunction "PD_PIN_8_CATHODE_8") (pintype "bidirectional"))
      (node (ref "IC1") (pin "D2") (pinfunction "PD3_IN_D2") (pintype "bidirectional"))
    )
    (net (code "31") (name "PGND") (class "Default")
      (node (ref "IC1") (pin "E1") (pinfunction "PGND_E1") (pintype "bidirectional"))
      (node (ref "R7") (pin "1") (pinfunction "1_1") (pintype "passive"))
    )
    (net (code "32") (name "RA") (class "Default")
      (node (ref "IC1") (pin "A6") (pinfunction "ECG_EL2_A6") (pintype "bidirectional"))
      (node (ref "JP1") (pin "1") (pinfunction "1_1") (pintype "passive"))
    )
    (net (code "33") (name "RLD") (class "Default")
      (node (ref "IC1") (pin "C6") (pinfunction "ECG_EL3_C6") (pintype "bidirectional"))
      (node (ref "JP1") (pin "3") (pinfunction "3_3") (pintype "passive"))
    )
    (net (code "34") (name "RST") (class "Default")
      (node (ref "C22") (pin "1") (pinfunction "1_1") (pintype "passive"))
      (node (ref "SW1") (pin "A") (pinfunction "P_A") (pintype "passive"))
      (node (ref "SW1") (pin "A'") (pinfunction "P1_A'") (pintype "passive"))
      (node (ref "U1") (pin "7") (pinfunction "NRST_7") (pintype "bidirectional"))
    )
    (net (code "35") (name "RX0") (class "Default")
      (node (ref "JP3") (pin "2") (pinfunction "2_2") (pintype "passive"))
      (node (ref "U1") (pin "17") (pinfunction "PA3_17") (pintype "bidirectional"))
    )
    (net (code "36") (name "RXBLE") (class "Default")
      (node (ref "JP5") (pin "1") (pinfunction "1_1") (pintype "passive"))
      (node (ref "JP6") (pin "5") (pinfunction "5_5") (pintype "passive"))
      (node (ref "U1") (pin "53") (pinfunction "PC12_53") (pintype "bidirectional"))
    )
    (net (code "37") (name "SCL") (class "Default")
      (node (ref "JP2") (pin "2") (pinfunction "2_2") (pintype "passive"))
      (node (ref "JP4") (pin "2") (pinfunction "2_2") (pintype "passive"))
      (node (ref "U1") (pin "50") (pinfunction "PA15_50") (pintype "bidirectional"))
    )
    (net (code "38") (name "SCLK") (class "Default")
      (node (ref "IC1") (pin "E4") (pinfunction "SCLK/SCL_E4") (pintype "bidirectional"))
      (node (ref "JP7") (pin "4") (pinfunction "4_4") (pintype "passive"))
      (node (ref "U1") (pin "34") (pinfunction "PB13_34") (pintype "bidirectional"))
    )
    (net (code "39") (name "SDA") (class "Default")
      (node (ref "JP2") (pin "1") (pinfunction "1_1") (pintype "passive"))
      (node (ref "JP4") (pin "1") (pinfunction "1_1") (pintype "passive"))
      (node (ref "U1") (pin "59") (pinfunction "PB7_59") (pintype "bidirectional"))
    )
    (net (code "40") (name "SWCLK") (class "Default")
      (node (ref "JP10") (pin "2") (pinfunction "2_2") (pintype "passive"))
      (node (ref "U1") (pin "49") (pinfunction "PA14_49") (pintype "bidirectional"))
    )
    (net (code "41") (name "SWIO") (class "Default")
      (node (ref "JP10") (pin "1") (pinfunction "1_1") (pintype "passive"))
      (node (ref "U1") (pin "46") (pinfunction "PA13_46") (pintype "bidirectional"))
    )
    (net (code "42") (name "TRIG") (class "Default")
      (node (ref "IC1") (pin "G6") (pinfunction "TRIG_G6") (pintype "bidirectional"))
      (node (ref "U1") (pin "55") (pinfunction "PB3_55") (pintype "bidirectional"))
    )
    (net (code "43") (name "TX0") (class "Default")
      (node (ref "JP3") (pin "1") (pinfunction "1_1") (pintype "passive"))
      (node (ref "U1") (pin "16") (pinfunction "PA2_16") (pintype "bidirectional"))
    )
    (net (code "44") (name "TXBLE") (class "Default")
      (node (ref "JP5") (pin "2") (pinfunction "2_2") (pintype "passive"))
      (node (ref "JP6") (pin "4") (pinfunction "4_4") (pintype "passive"))
      (node (ref "U1") (pin "54") (pinfunction "PD2_54") (pintype "bidirectional"))
    )
    (net (code "45") (name "VBAT") (class "Default")
      (node (ref "JP8") (pin "2") (pinfunction "2_2") (pintype "passive"))
      (node (ref "U1") (pin "1") (pinfunction "VBAT_1") (pintype "power_in"))
    )
    (net (code "46") (name "VMID_ECG") (class "Default")
      (node (ref "C1") (pin "2") (pinfunction "2_2") (pintype "passive"))
      (node (ref "IC1") (pin "E6") (pinfunction "VMID_ECG_E6") (pintype "bidirectional"))
    )
    (net (code "47") (name "VREF_ECG") (class "Default")
      (node (ref "C3") (pin "2") (pinfunction "2_2") (pintype "passive"))
      (node (ref "IC1") (pin "F6") (pinfunction "VREF_ECG_F6") (pintype "bidirectional"))
    )
    (net (code "48") (name "VREF_PPG") (class "Default")
      (node (ref "C2") (pin "2") (pinfunction "2_2") (pintype "passive"))
      (node (ref "IC1") (pin "E2") (pinfunction "VREF_PPG_E2") (pintype "bidirectional"))
    )
    (net (code "49") (name "unconnected-(IC1-BIOZ_EL1-PadA3)") (class "Default")
      (node (ref "IC1") (pin "A3") (pinfunction "BIOZ_EL1_A3") (pintype "bidirectional"))
    )
    (net (code "50") (name "unconnected-(IC1-BIOZ_EL2A-PadA1)") (class "Default")
      (node (ref "IC1") (pin "A1") (pinfunction "BIOZ_EL2A_A1") (pintype "bidirectional"))
    )
    (net (code "51") (name "unconnected-(IC1-BIOZ_EL2B-PadB1)") (class "Default")
      (node (ref "IC1") (pin "B1") (pinfunction "BIOZ_EL2B_B1") (pintype "bidirectional"))
    )
    (net (code "52") (name "unconnected-(IC1-BIOZ_EL3A-PadA2)") (class "Default")
      (node (ref "IC1") (pin "A2") (pinfunction "BIOZ_EL3A_A2") (pintype "bidirectional"))
    )
    (net (code "53") (name "unconnected-(IC1-BIOZ_EL3B-PadB2)") (class "Default")
      (node (ref "IC1") (pin "B2") (pinfunction "BIOZ_EL3B_B2") (pintype "bidirectional"))
    )
    (net (code "54") (name "unconnected-(IC1-BIOZ_EL4-PadA4)") (class "Default")
      (node (ref "IC1") (pin "A4") (pinfunction "BIOZ_EL4_A4") (pintype "bidirectional"))
    )
    (net (code "55") (name "unconnected-(IC1-CAL1-PadA5)") (class "Default")
      (node (ref "IC1") (pin "A5") (pinfunction "CAL1_A5") (pintype "bidirectional"))
    )
    (net (code "56") (name "unconnected-(IC1-CAL2-PadB5)") (class "Default")
      (node (ref "IC1") (pin "B5") (pinfunction "CAL2_B5") (pintype "bidirectional"))
    )
    (net (code "57") (name "unconnected-(IC1-CAL3-PadB4)") (class "Default")
      (node (ref "IC1") (pin "B4") (pinfunction "CAL3_B4") (pintype "bidirectional"))
    )
    (net (code "58") (name "unconnected-(IC1-CAL4-PadB3)") (class "Default")
      (node (ref "IC1") (pin "B3") (pinfunction "CAL4_B3") (pintype "bidirectional"))
    )
    (net (code "59") (name "unconnected-(IC1-DRVSJ-PadC5)") (class "Default")
      (node (ref "IC1") (pin "C5") (pinfunction "DRVSJ_C5") (pintype "bidirectional"))
    )
    (net (code "60") (name "unconnected-(IC1-DRVXC-PadD5)") (class "Default")
      (node (ref "IC1") (pin "D5") (pinfunction "DRVXC_D5") (pintype "bidirectional"))
    )
    (net (code "61") (name "unconnected-(IC1-DRVXR-PadC4)") (class "Default")
      (node (ref "IC1") (pin "C4") (pinfunction "DRVXR_C4") (pintype "bidirectional"))
    )
    (net (code "62") (name "unconnected-(IC1-FCLK-PadF5)") (class "Default")
      (node (ref "IC1") (pin "F5") (pinfunction "FCLK_F5") (pintype "bidirectional"))
    )
    (net (code "63") (name "unconnected-(IC1-LDO_OUT-PadE7)") (class "Default")
      (node (ref "IC1") (pin "E7") (pinfunction "LDO_OUT_E7") (pintype "bidirectional"))
    )
    (net (code "64") (name "unconnected-(IC1-LED4_DRV-PadF2)") (class "Default")
      (node (ref "IC1") (pin "F2") (pinfunction "LED4_DRV_F2") (pintype "bidirectional"))
    )
    (net (code "65") (name "unconnected-(IC1-LED5_DRV-PadG1)") (class "Default")
      (node (ref "IC1") (pin "G1") (pinfunction "LED5_DRV_G1") (pintype "bidirectional"))
    )
    (net (code "66") (name "unconnected-(IC1-LED6_DRV-PadF1)") (class "Default")
      (node (ref "IC1") (pin "F1") (pinfunction "LED6_DRV_F1") (pintype "bidirectional"))
    )
    (net (code "67") (name "unconnected-(IC1-PD4_IN-PadC2)") (class "Default")
      (node (ref "IC1") (pin "C2") (pinfunction "PD4_IN_C2") (pintype "bidirectional"))
    )
    (net (code "68") (name "unconnected-(IC1-RLD_INV-PadC7)") (class "Default")
      (node (ref "IC1") (pin "C7") (pinfunction "RLD_INV_C7") (pintype "bidirectional"))
    )
    (net (code "69") (name "unconnected-(J2-CC1-PadA5)") (class "Default")
      (node (ref "J2") (pin "A5") (pinfunction "CC1_A5") (pintype "bidirectional"))
    )
    (net (code "70") (name "unconnected-(J2-CC2-PadB5)") (class "Default")
      (node (ref "J2") (pin "B5") (pinfunction "CC2_B5") (pintype "bidirectional"))
    )
    (net (code "71") (name "unconnected-(J2-DN1-PadA7)") (class "Default")
      (node (ref "J2") (pin "A7") (pinfunction "DN1_A7") (pintype "bidirectional"))
    )
    (net (code "72") (name "unconnected-(J2-DN2-PadB7)") (class "Default")
      (node (ref "J2") (pin "B7") (pinfunction "DN2_B7") (pintype "bidirectional"))
    )
    (net (code "73") (name "unconnected-(J2-DP1-PadA6)") (class "Default")
      (node (ref "J2") (pin "A6") (pinfunction "DP1_A6") (pintype "bidirectional"))
    )
    (net (code "74") (name "unconnected-(J2-DP2-PadB6)") (class "Default")
      (node (ref "J2") (pin "B6") (pinfunction "DP2_B6") (pintype "bidirectional"))
    )
    (net (code "75") (name "unconnected-(J2-SBU1-PadA8)") (class "Default")
      (node (ref "J2") (pin "A8") (pinfunction "SBU1_A8") (pintype "bidirectional"))
    )
    (net (code "76") (name "unconnected-(J2-SBU2-PadB8)") (class "Default")
      (node (ref "J2") (pin "B8") (pinfunction "SBU2_B8") (pintype "bidirectional"))
    )
    (net (code "77") (name "unconnected-(J2-SSRXN1-PadB10)") (class "Default")
      (node (ref "J2") (pin "B10") (pinfunction "SSRXN1_B10") (pintype "bidirectional"))
    )
    (net (code "78") (name "unconnected-(J2-SSRXN2-PadA10)") (class "Default")
      (node (ref "J2") (pin "A10") (pinfunction "SSRXN2_A10") (pintype "bidirectional"))
    )
    (net (code "79") (name "unconnected-(J2-SSRXP1-PadB11)") (class "Default")
      (node (ref "J2") (pin "B11") (pinfunction "SSRXP1_B11") (pintype "bidirectional"))
    )
    (net (code "80") (name "unconnected-(J2-SSRXP2-PadA11)") (class "Default")
      (node (ref "J2") (pin "A11") (pinfunction "SSRXP2_A11") (pintype "bidirectional"))
    )
    (net (code "81") (name "unconnected-(J2-SSTXN1-PadA3)") (class "Default")
      (node (ref "J2") (pin "A3") (pinfunction "SSTXN1_A3") (pintype "bidirectional"))
    )
    (net (code "82") (name "unconnected-(J2-SSTXN2-PadB3)") (class "Default")
      (node (ref "J2") (pin "B3") (pinfunction "SSTXN2_B3") (pintype "bidirectional"))
    )
    (net (code "83") (name "unconnected-(J2-SSTXP1-PadA2)") (class "Default")
      (node (ref "J2") (pin "A2") (pinfunction "SSTXP1_A2") (pintype "bidirectional"))
    )
    (net (code "84") (name "unconnected-(J2-SSTXP2-PadB2)") (class "Default")
      (node (ref "J2") (pin "B2") (pinfunction "SSTXP2_B2") (pintype "bidirectional"))
    )
    (net (code "85") (name "unconnected-(JP6-Pad1)") (class "Default")
      (node (ref "JP6") (pin "1") (pinfunction "1_1") (pintype "passive"))
    )
    (net (code "86") (name "unconnected-(JP6-Pad6)") (class "Default")
      (node (ref "JP6") (pin "6") (pinfunction "6_6") (pintype "passive"))
    )
    (net (code "87") (name "unconnected-(LED1-NC-Pad6)") (class "Default")
      (node (ref "LED1") (pin "6") (pinfunction "NC_6") (pintype "no_connect"))
    )
    (net (code "88") (name "unconnected-(R8-Pad1)") (class "Default")
      (node (ref "R8") (pin "1") (pinfunction "1_1") (pintype "passive"))
    )
    (net (code "89") (name "unconnected-(U1-PA0-Pad14)") (class "Default")
      (node (ref "U1") (pin "14") (pinfunction "PA0_14") (pintype "bidirectional"))
    )
    (net (code "90") (name "unconnected-(U1-PA1-Pad15)") (class "Default")
      (node (ref "U1") (pin "15") (pinfunction "PA1_15") (pintype "bidirectional"))
    )
    (net (code "91") (name "unconnected-(U1-PA4-Pad20)") (class "Default")
      (node (ref "U1") (pin "20") (pinfunction "PA4_20") (pintype "bidirectional"))
    )
    (net (code "92") (name "unconnected-(U1-PA6-Pad22)") (class "Default")
      (node (ref "U1") (pin "22") (pinfunction "PA6_22") (pintype "bidirectional"))
    )
    (net (code "93") (name "unconnected-(U1-PA7-Pad23)") (class "Default")
      (node (ref "U1") (pin "23") (pinfunction "PA7_23") (pintype "bidirectional"))
    )
    (net (code "94") (name "unconnected-(U1-PA8-Pad41)") (class "Default")
      (node (ref "U1") (pin "41") (pinfunction "PA8_41") (pintype "bidirectional"))
    )
    (net (code "95") (name "unconnected-(U1-PA9-Pad42)") (class "Default")
      (node (ref "U1") (pin "42") (pinfunction "PA9_42") (pintype "bidirectional"))
    )
    (net (code "96") (name "unconnected-(U1-PA10-Pad43)") (class "Default")
      (node (ref "U1") (pin "43") (pinfunction "PA10_43") (pintype "bidirectional"))
    )
    (net (code "97") (name "unconnected-(U1-PA11-Pad44)") (class "Default")
      (node (ref "U1") (pin "44") (pinfunction "PA11_44") (pintype "bidirectional"))
    )
    (net (code "98") (name "unconnected-(U1-PA12-Pad45)") (class "Default")
      (node (ref "U1") (pin "45") (pinfunction "PA12_45") (pintype "bidirectional"))
    )
    (net (code "99") (name "unconnected-(U1-PB0-Pad26)") (class "Default")
      (node (ref "U1") (pin "26") (pinfunction "PB0_26") (pintype "bidirectional"))
    )
    (net (code "100") (name "unconnected-(U1-PB2-Pad28)") (class "Default")
      (node (ref "U1") (pin "28") (pinfunction "PB2_28") (pintype "bidirectional"))
    )
    (net (code "101") (name "unconnected-(U1-PB4-Pad56)") (class "Default")
      (node (ref "U1") (pin "56") (pinfunction "PB4_56") (pintype "bidirectional"))
    )
    (net (code "102") (name "unconnected-(U1-PB5-Pad57)") (class "Default")
      (node (ref "U1") (pin "57") (pinfunction "PB5_57") (pintype "bidirectional"))
    )
    (net (code "103") (name "unconnected-(U1-PB6-Pad58)") (class "Default")
      (node (ref "U1") (pin "58") (pinfunction "PB6_58") (pintype "bidirectional"))
    )
    (net (code "104") (name "unconnected-(U1-PB8-Pad61)") (class "Default")
      (node (ref "U1") (pin "61") (pinfunction "PB8_61") (pintype "bidirectional"))
    )
    (net (code "105") (name "unconnected-(U1-PB9-Pad62)") (class "Default")
      (node (ref "U1") (pin "62") (pinfunction "PB9_62") (pintype "bidirectional"))
    )
    (net (code "106") (name "unconnected-(U1-PB10-Pad29)") (class "Default")
      (node (ref "U1") (pin "29") (pinfunction "PB10_29") (pintype "bidirectional"))
    )
    (net (code "107") (name "unconnected-(U1-PB11-Pad30)") (class "Default")
      (node (ref "U1") (pin "30") (pinfunction "PB11_30") (pintype "bidirectional"))
    )
    (net (code "108") (name "unconnected-(U1-PB12-Pad33)") (class "Default")
      (node (ref "U1") (pin "33") (pinfunction "PB12_33") (pintype "bidirectional"))
    )
    (net (code "109") (name "unconnected-(U1-PC2-Pad10)") (class "Default")
      (node (ref "U1") (pin "10") (pinfunction "PC2_10") (pintype "bidirectional"))
    )
    (net (code "110") (name "unconnected-(U1-PC3-Pad11)") (class "Default")
      (node (ref "U1") (pin "11") (pinfunction "PC3_11") (pintype "bidirectional"))
    )
    (net (code "111") (name "unconnected-(U1-PC4-Pad24)") (class "Default")
      (node (ref "U1") (pin "24") (pinfunction "PC4_24") (pintype "bidirectional"))
    )
    (net (code "112") (name "unconnected-(U1-PC5-Pad25)") (class "Default")
      (node (ref "U1") (pin "25") (pinfunction "PC5_25") (pintype "bidirectional"))
    )
    (net (code "113") (name "unconnected-(U1-PC6-Pad37)") (class "Default")
      (node (ref "U1") (pin "37") (pinfunction "PC6_37") (pintype "bidirectional"))
    )
    (net (code "114") (name "unconnected-(U1-PC7-Pad38)") (class "Default")
      (node (ref "U1") (pin "38") (pinfunction "PC7_38") (pintype "bidirectional"))
    )
    (net (code "115") (name "unconnected-(U1-PC8-Pad39)") (class "Default")
      (node (ref "U1") (pin "39") (pinfunction "PC8_39") (pintype "bidirectional"))
    )
    (net (code "116") (name "unconnected-(U1-PC9-Pad40)") (class "Default")
      (node (ref "U1") (pin "40") (pinfunction "PC9_40") (pintype "bidirectional"))
    )
    (net (code "117") (name "unconnected-(U1-PC10-Pad51)") (class "Default")
      (node (ref "U1") (pin "51") (pinfunction "PC10_51") (pintype "bidirectional"))
    )
    (net (code "118") (name "unconnected-(U1-PC11-Pad52)") (class "Default")
      (node (ref "U1") (pin "52") (pinfunction "PC11_52") (pintype "bidirectional"))
    )
    (net (code "119") (name "unconnected-(U1-PC13-Pad2)") (class "Default")
      (node (ref "U1") (pin "2") (pinfunction "PC13_2") (pintype "bidirectional"))
    )
    (net (code "120") (name "unconnected-(U1-PF0-OSC-IN-Pad5)") (class "Default")
      (node (ref "U1") (pin "5") (pinfunction "PF0-OSC-IN_5") (pintype "bidirectional"))
    )
  )
)
